# SCH_N3_FLIGHT_COMPUTER_2023-10-18.net
KiCad netlist of a schematic drawn in EasyEDA
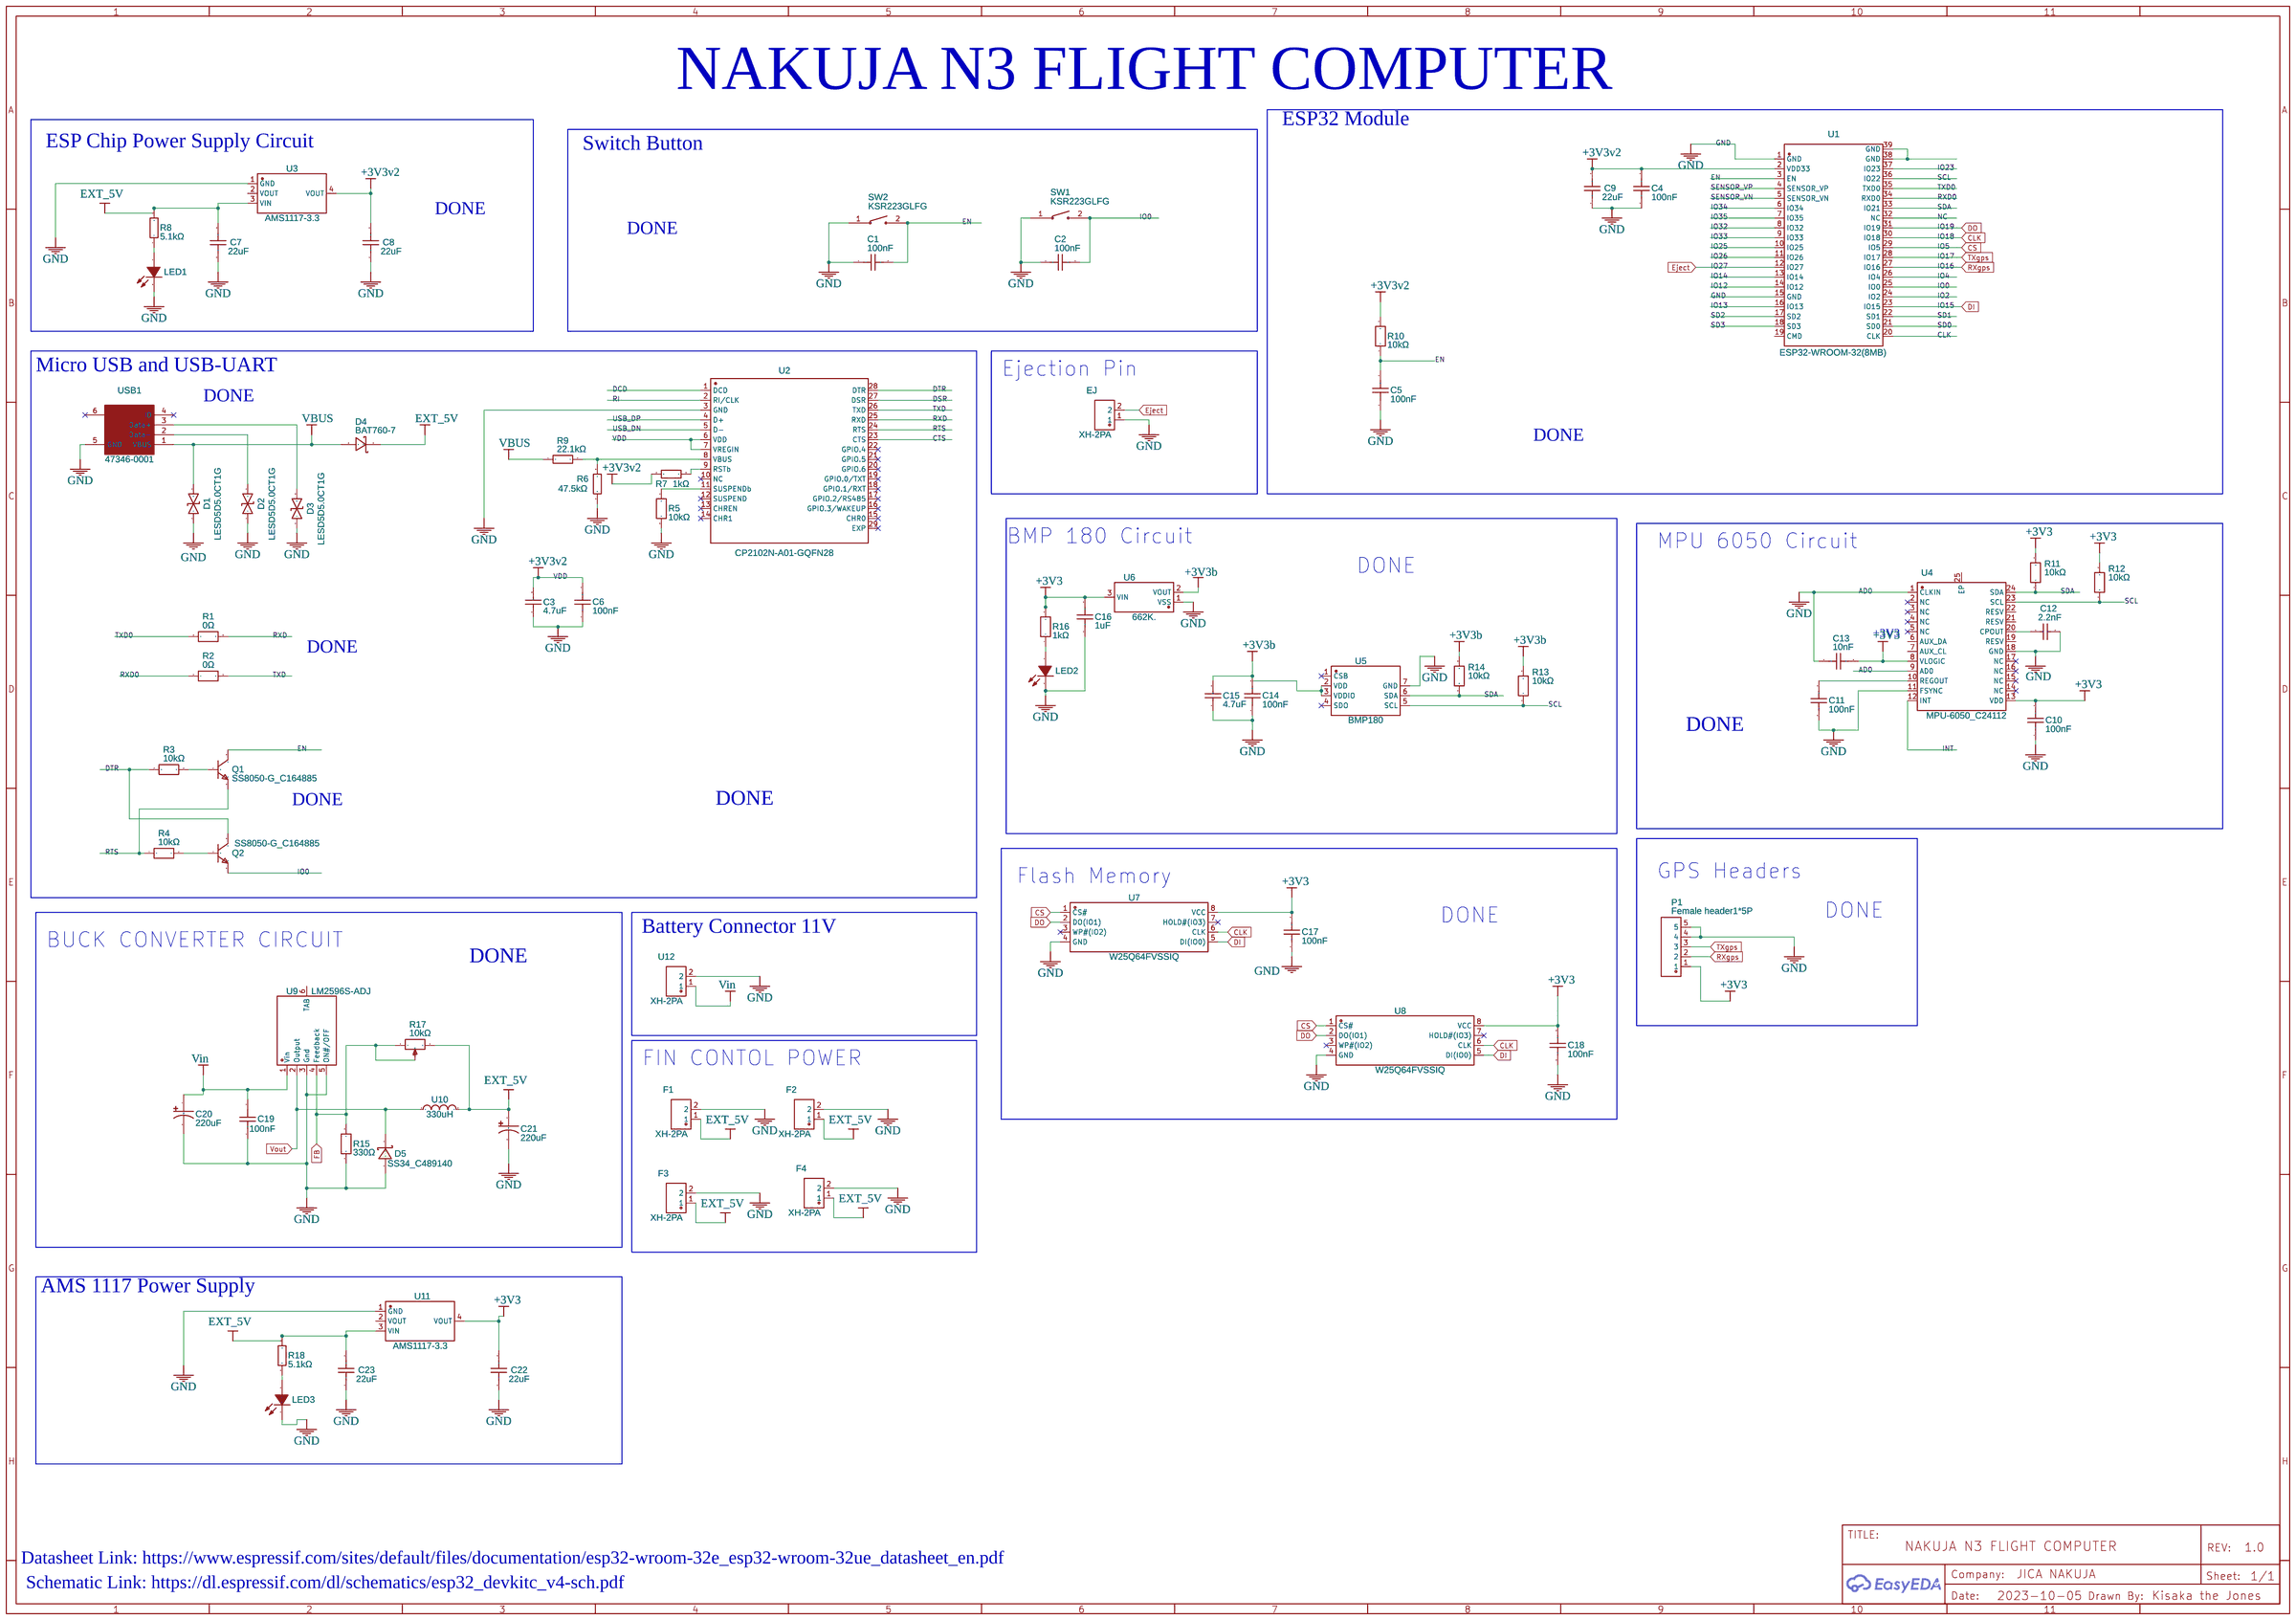
[diagram p0: schematic sheet]

(export (version "E")
  (design (tool "Eeschema 10.0.6"))
  (components
    (comp (ref "C1")
      (value "100nF")
      (fields
        (field (name "Manufacturer Part") "CL05A104KA5NNND")
        (field (name "Manufacturer") "SAMSUNG(三星)")
      )
      (libsource (lib "") (part "CL05A104KA5NNND_1"))
    )
    (comp (ref "C2")
      (value "100nF")
      (fields
        (field (name "Manufacturer Part") "CL05A104KA5NNND")
        (field (name "Manufacturer") "SAMSUNG(三星)")
      )
      (libsource (lib "") (part "CL05A104KA5NNND_1"))
    )
    (comp (ref "C3")
      (value "4.7uF")
      (fields
        (field (name "Manufacturer Part") "CL21B475KPFNNNE")
        (field (name "Manufacturer") "SAMSUNG(三星)")
      )
      (libsource (lib "") (part "CL21B475KPFNNNE"))
    )
    (comp (ref "C4")
      (value "100nF")
      (fields
        (field (name "Manufacturer Part") "CL05A104KA5NNND")
        (field (name "Manufacturer") "SAMSUNG(三星)")
      )
      (libsource (lib "") (part "CL05A104KA5NNND"))
    )
    (comp (ref "C5")
      (value "100nF")
      (fields
        (field (name "Manufacturer Part") "CL05A104KA5NNND")
        (field (name "Manufacturer") "SAMSUNG(三星)")
      )
      (libsource (lib "") (part "CL05A104KA5NNND"))
    )
    (comp (ref "C6")
      (value "100nF")
      (fields
        (field (name "Manufacturer Part") "CL05A104KA5NNND")
        (field (name "Manufacturer") "SAMSUNG(三星)")
      )
      (libsource (lib "") (part "CL05A104KA5NNND"))
    )
    (comp (ref "C7")
      (value "22uF")
      (fields
        (field (name "Manufacturer Part") "CL21A226MAQNNNF")
        (field (name "Manufacturer") "SAMSUNG(三星)")
      )
      (libsource (lib "") (part "CL21A226MAQNNNF"))
    )
    (comp (ref "C8")
      (value "22uF")
      (fields
        (field (name "Manufacturer Part") "CL21A226MAQNNNF")
        (field (name "Manufacturer") "SAMSUNG(三星)")
      )
      (libsource (lib "") (part "CL21A226MAQNNNF"))
    )
    (comp (ref "C9")
      (value "22uF")
      (fields
        (field (name "Manufacturer Part") "CL21A226MAQNNNF")
        (field (name "Manufacturer") "SAMSUNG(三星)")
      )
      (libsource (lib "") (part "CL21A226MAQNNNF"))
    )
    (comp (ref "C10")
      (value "100nF")
      (fields
        (field (name "Manufacturer Part") "CL05A104KA5NNND")
        (field (name "Manufacturer") "SAMSUNG(三星)")
      )
      (libsource (lib "") (part "CL05A104KA5NNND"))
    )
    (comp (ref "C11")
      (value "100nF")
      (fields
        (field (name "Manufacturer Part") "CL05A104KA5NNND")
        (field (name "Manufacturer") "SAMSUNG(三星)")
      )
      (libsource (lib "") (part "CL05A104KA5NNND"))
    )
    (comp (ref "C12")
      (value "2.2nF")
      (fields (field (name "Manufacturer Part") "0805B222K500NT") (field (name "Manufacturer") "FH(风华)"))
      (libsource (lib "") (part "0805B222K500NT"))
    )
    (comp (ref "C13")
      (value "10nF")
      (fields
        (field (name "Manufacturer Part") "CC0805KRX7R9BB103")
        (field (name "Manufacturer") "YAGEO(国巨)")
      )
      (libsource (lib "") (part "CC0805KRX7R9BB103"))
    )
    (comp (ref "C14")
      (value "100nF")
      (fields
        (field (name "Manufacturer Part") "CL05A104KA5NNND")
        (field (name "Manufacturer") "SAMSUNG(三星)")
      )
      (libsource (lib "") (part "CL05A104KA5NNND"))
    )
    (comp (ref "C15")
      (value "4.7uF")
      (fields
        (field (name "Manufacturer Part") "CL21B475KPFNNNE")
        (field (name "Manufacturer") "SAMSUNG(三星)")
      )
      (libsource (lib "") (part "CL21B475KPFNNNE"))
    )
    (comp (ref "C16")
      (value "1uF")
      (fields
        (field (name "Manufacturer Part") "CL21B105KBFNFNE")
        (field (name "Manufacturer") "SAMSUNG(三星)")
      )
      (libsource (lib "") (part "CL21B105KBFNFNE"))
    )
    (comp (ref "C17")
      (value "100nF")
      (fields
        (field (name "Manufacturer Part") "CL05A104KA5NNND")
        (field (name "Manufacturer") "SAMSUNG(三星)")
      )
      (libsource (lib "") (part "CL05A104KA5NNND"))
    )
    (comp (ref "C18")
      (value "100nF")
      (fields
        (field (name "Manufacturer Part") "CL05A104KA5NNND")
        (field (name "Manufacturer") "SAMSUNG(三星)")
      )
      (libsource (lib "") (part "CL05A104KA5NNND"))
    )
    (comp (ref "C19")
      (value "100nF")
      (fields
        (field (name "Manufacturer Part") "CL05A104KA5NNND")
        (field (name "Manufacturer") "SAMSUNG(三星)")
      )
      (libsource (lib "") (part "CL05A104KA5NNND"))
    )
    (comp (ref "C20")
      (value "220uF")
      (fields (field (name "Manufacturer Part") "EEEFP1H221AP") (field (name "Manufacturer") "PANASONIC(松下)"))
      (libsource (lib "") (part "EEEFP1H221AP_1"))
    )
    (comp (ref "C21")
      (value "220uF")
      (fields (field (name "Manufacturer Part") "EEEFP1H221AP") (field (name "Manufacturer") "PANASONIC(松下)"))
      (libsource (lib "") (part "EEEFP1H221AP"))
    )
    (comp (ref "C22")
      (value "22uF")
      (fields
        (field (name "Manufacturer Part") "CL21A226MAQNNNF")
        (field (name "Manufacturer") "SAMSUNG(三星)")
      )
      (libsource (lib "") (part "CL21A226MAQNNNF"))
    )
    (comp (ref "C23")
      (value "22uF")
      (fields
        (field (name "Manufacturer Part") "CL21A226MAQNNNF")
        (field (name "Manufacturer") "SAMSUNG(三星)")
      )
      (libsource (lib "") (part "CL21A226MAQNNNF"))
    )
    (comp (ref "D1")
      (value "LESD5D5.0CT1G")
      (fields (field (name "Manufacturer") "LRC(乐山无线电)"))
      (libsource (lib "") (part "LESD5D5.0CT1G"))
    )
    (comp (ref "D2")
      (value "LESD5D5.0CT1G")
      (fields (field (name "Manufacturer") "LRC(乐山无线电)"))
      (libsource (lib "") (part "LESD5D5.0CT1G"))
    )
    (comp (ref "D3")
      (value "LESD5D5.0CT1G")
      (fields (field (name "Manufacturer") "LRC(乐山无线电)"))
      (libsource (lib "") (part "LESD5D5.0CT1G"))
    )
    (comp (ref "D4")
      (value "BAT760-7")
      (fields (field (name "Manufacturer") "DIODES(美台)"))
      (libsource (lib "") (part "BAT760-7"))
    )
    (comp (ref "D5")
      (value "SS34_C489140")
      (fields (field (name "Manufacturer Part") "SS34") (field (name "Manufacturer") "KEXIN(科信)"))
      (libsource (lib "") (part "SS34_C489140"))
    )
    (comp (ref "EJ")
      (value "XH-2PA")
      (fields (field (name "Manufacturer") "ZHOURI(洲日)"))
      (libsource (lib "") (part "XH-2PA_2"))
    )
    (comp (ref "F1")
      (value "XH-2PA")
      (fields (field (name "Manufacturer") "ZHOURI(洲日)"))
      (libsource (lib "") (part "XH-2PA"))
    )
    (comp (ref "F2")
      (value "XH-2PA")
      (fields (field (name "Manufacturer") "ZHOURI(洲日)"))
      (libsource (lib "") (part "XH-2PA"))
    )
    (comp (ref "F3")
      (value "XH-2PA")
      (fields (field (name "Manufacturer") "ZHOURI(洲日)"))
      (libsource (lib "") (part "XH-2PA"))
    )
    (comp (ref "F4")
      (value "XH-2PA")
      (fields (field (name "Manufacturer") "ZHOURI(洲日)"))
      (libsource (lib "") (part "XH-2PA"))
    )
    (comp (ref "LED1")
      (value "15-21SOC/TR8")
      (fields (field (name "Manufacturer") "EVERLIGHT(亿光)"))
      (libsource (lib "") (part "15-21SOC/TR8"))
    )
    (comp (ref "LED2")
      (value "15-21SOC/TR8")
      (fields (field (name "Manufacturer") "EVERLIGHT(亿光)"))
      (libsource (lib "") (part "15-21SOC/TR8"))
    )
    (comp (ref "LED3")
      (value "15-21SOC/TR8")
      (fields (field (name "Manufacturer") "EVERLIGHT(亿光)"))
      (libsource (lib "") (part "15-21SOC/TR8"))
    )
    (comp (ref "P1")
      (value "Female header1*5P")
      (fields (field (name "Manufacturer Part") "2.0-1*5P母") (field (name "Manufacturer") "BOOMELE(博穆精密)"))
      (libsource (lib "") (part "Female header1*5P"))
    )
    (comp (ref "Q1")
      (value "SS8050-G_C164885")
      (fields (field (name "Manufacturer Part") "SS8050-G") (field (name "Manufacturer") "CJ(江苏长电/长晶)"))
      (libsource (lib "") (part "SS8050-G_C164885"))
    )
    (comp (ref "Q2")
      (value "SS8050-G_C164885")
      (fields (field (name "Manufacturer Part") "SS8050-G") (field (name "Manufacturer") "CJ(江苏长电/长晶)"))
      (libsource (lib "") (part "SS8050-G_C164885"))
    )
    (comp (ref "R1")
      (value "0Ω")
      (fields (field (name "Manufacturer Part") "SY0402JN0RP") (field (name "Manufacturer") "SANYEAR(叁叶源)"))
      (libsource (lib "") (part "SY0402JN0RP"))
    )
    (comp (ref "R2")
      (value "0Ω")
      (fields (field (name "Manufacturer Part") "SY0402JN0RP") (field (name "Manufacturer") "SANYEAR(叁叶源)"))
      (libsource (lib "") (part "SY0402JN0RP"))
    )
    (comp (ref "R3")
      (value "10kΩ")
      (fields
        (field (name "Manufacturer Part") "RMC1/10-103JTP")
        (field (name "Manufacturer") "KAMAYA(釜屋電機)")
      )
      (libsource (lib "") (part "RMC1/10-103JTP_1"))
    )
    (comp (ref "R4")
      (value "10kΩ")
      (fields
        (field (name "Manufacturer Part") "RMC1/10-103JTP")
        (field (name "Manufacturer") "KAMAYA(釜屋電機)")
      )
      (libsource (lib "") (part "RMC1/10-103JTP_1"))
    )
    (comp (ref "R5")
      (value "10kΩ")
      (fields
        (field (name "Manufacturer Part") "RMC1/10-103JTP")
        (field (name "Manufacturer") "KAMAYA(釜屋電機)")
      )
      (libsource (lib "") (part "RMC1/10-103JTP_2"))
    )
    (comp (ref "R6")
      (value "47.5kΩ")
      (fields
        (field (name "Manufacturer Part") "0402WGF4752TCE")
        (field (name "Manufacturer") "UNI-ROYAL(厚声)")
      )
      (libsource (lib "") (part "0402WGF4752TCE"))
    )
    (comp (ref "R7")
      (value "1kΩ")
      (fields
        (field (name "Manufacturer Part") "0402WGF1001TCE")
        (field (name "Manufacturer") "UNI-ROYAL(厚声)")
      )
      (libsource (lib "") (part "0402WGF1001TCE"))
    )
    (comp (ref "R8")
      (value "5.1kΩ")
      (fields
        (field (name "Manufacturer Part") "0402WGJ0512TCE")
        (field (name "Manufacturer") "UNI-ROYAL(厚声)")
      )
      (libsource (lib "") (part "0402WGJ0512TCE"))
    )
    (comp (ref "R9")
      (value "22.1kΩ")
      (fields
        (field (name "Manufacturer Part") "0402WGF2212TCE")
        (field (name "Manufacturer") "UNI-ROYAL(厚声)")
      )
      (libsource (lib "") (part "0402WGF2212TCE"))
    )
    (comp (ref "R10")
      (value "10kΩ")
      (fields
        (field (name "Manufacturer Part") "RMC1/10-103JTP")
        (field (name "Manufacturer") "KAMAYA(釜屋電機)")
      )
      (libsource (lib "") (part "RMC1/10-103JTP"))
    )
    (comp (ref "R11")
      (value "10kΩ")
      (fields
        (field (name "Manufacturer Part") "RMC1/10-103JTP")
        (field (name "Manufacturer") "KAMAYA(釜屋電機)")
      )
      (libsource (lib "") (part "RMC1/10-103JTP"))
    )
    (comp (ref "R12")
      (value "10kΩ")
      (fields
        (field (name "Manufacturer Part") "RMC1/10-103JTP")
        (field (name "Manufacturer") "KAMAYA(釜屋電機)")
      )
      (libsource (lib "") (part "RMC1/10-103JTP"))
    )
    (comp (ref "R13")
      (value "10kΩ")
      (fields
        (field (name "Manufacturer Part") "RMC1/10-103JTP")
        (field (name "Manufacturer") "KAMAYA(釜屋電機)")
      )
      (libsource (lib "") (part "RMC1/10-103JTP"))
    )
    (comp (ref "R14")
      (value "10kΩ")
      (fields
        (field (name "Manufacturer Part") "RMC1/10-103JTP")
        (field (name "Manufacturer") "KAMAYA(釜屋電機)")
      )
      (libsource (lib "") (part "RMC1/10-103JTP"))
    )
    (comp (ref "R15")
      (value "330Ω")
      (fields
        (field (name "Manufacturer Part") "SYLE1206JN330RP")
        (field (name "Manufacturer") "SANYEAR(叁叶源)")
      )
      (libsource (lib "") (part "SYLE1206JN330RP"))
    )
    (comp (ref "R16")
      (value "1kΩ")
      (fields (field (name "Manufacturer Part") "WR08X102JTL") (field (name "Manufacturer") "Walsin(华新科)"))
      (libsource (lib "") (part "WR08X102 JTL"))
    )
    (comp (ref "R17")
      (value "10kΩ")
      (fields (field (name "Manufacturer Part") "3296W-1-103LF") (field (name "Manufacturer") "BOURNS"))
      (libsource (lib "") (part "3296W-1-103LF"))
    )
    (comp (ref "R18")
      (value "5.1kΩ")
      (fields
        (field (name "Manufacturer Part") "0402WGJ0512TCE")
        (field (name "Manufacturer") "UNI-ROYAL(厚声)")
      )
      (libsource (lib "") (part "0402WGJ0512TCE"))
    )
    (comp (ref "SW1")
      (value "KSR223GLFG")
      (fields (field (name "Manufacturer") "C&K"))
      (libsource (lib "") (part "KSR223GLFG"))
    )
    (comp (ref "SW2")
      (value "KSR223GLFG")
      (fields (field (name "Manufacturer") "C&K"))
      (libsource (lib "") (part "KSR223GLFG"))
    )
    (comp (ref "U1")
      (value "ESP32-WROOM-32(8MB)")
      (fields
        (field (name "Manufacturer Part") "ESP32-WROOM-32-N8")
        (field (name "Manufacturer") "ESPRESSIF(乐鑫)")
      )
      (libsource (lib "") (part "ESP32-WROOM-32(8MB)"))
    )
    (comp (ref "U2")
      (value "CP2102N-A01-GQFN28")
      (fields
        (field (name "Manufacturer Part") "CP2102N-A01-GQFN28R")
        (field (name "Manufacturer") "SILICON LABS(芯科)")
      )
      (libsource (lib "") (part "CP2102N-A01-GQFN28"))
    )
    (comp (ref "U3")
      (value "AMS1117-3.3")
      (fields (field (name "Manufacturer") "AMS"))
      (libsource (lib "") (part "AMS1117-3.3"))
    )
    (comp (ref "U4")
      (value "MPU-6050_C24112")
      (fields
        (field (name "Manufacturer Part") "MPU-6050")
        (field (name "Manufacturer") "TDK InvenSense(应美盛)")
      )
      (libsource (lib "") (part "MPU-6050_C24112"))
    )
    (comp (ref "U5")
      (value "BMP180")
      (fields (field (name "Manufacturer") "Bosch(博世)"))
      (libsource (lib "") (part "BMP180"))
    )
    (comp (ref "U6")
      (value "662K.")
      (fields (field (name "Manufacturer") "FM(富满)"))
      (libsource (lib "") (part "662K."))
    )
    (comp (ref "U7")
      (value "W25Q64FVSSIQ")
      (fields (field (name "Manufacturer") "WINBOND(华邦)"))
      (libsource (lib "") (part "W25Q64FVSSIQ"))
    )
    (comp (ref "U8")
      (value "W25Q64FVSSIQ")
      (fields (field (name "Manufacturer") "WINBOND(华邦)"))
      (libsource (lib "") (part "W25Q64FVSSIQ"))
    )
    (comp (ref "U9")
      (value "LM2596S-ADJ")
      (fields (field (name "Manufacturer") "UMW(友台半导体)"))
      (libsource (lib "") (part "LM2596S-ADJ"))
    )
    (comp (ref "U10")
      (value "330uH")
      (fields (field (name "Manufacturer Part") "SLF12575T-331M1R0-H") (field (name "Manufacturer") "TDK"))
      (libsource (lib "") (part "SLF12575T-331M1R0-H"))
    )
    (comp (ref "U11")
      (value "AMS1117-3.3")
      (fields (field (name "Manufacturer") "AMS"))
      (libsource (lib "") (part "AMS1117-3.3"))
    )
    (comp (ref "U12")
      (value "XH-2PA")
      (fields (field (name "Manufacturer") "ZHOURI(洲日)"))
      (libsource (lib "") (part "XH-2PA_1"))
    )
    (comp (ref "USB1")
      (value "47346-0001")
      (fields (field (name "Manufacturer Part") "473460001") (field (name "Manufacturer") "MOLEX"))
      (libsource (lib "") (part "47346-0001"))
    )
  )
  (nets
    (net (code "1") (name "+3V3") (class "Default")
      (node (ref "C10") (pin "2") (pinfunction "2_2") (pintype "unspecified"))
      (node (ref "C13") (pin "2") (pinfunction "2_2") (pintype "unspecified"))
      (node (ref "C16") (pin "2") (pinfunction "2_2") (pintype "unspecified"))
      (node (ref "C17") (pin "2") (pinfunction "2_2") (pintype "unspecified"))
      (node (ref "C18") (pin "2") (pinfunction "2_2") (pintype "unspecified"))
      (node (ref "C22") (pin "2") (pinfunction "2_2") (pintype "unspecified"))
      (node (ref "P1") (pin "1") (pinfunction "1_1") (pintype "unspecified"))
      (node (ref "R11") (pin "2") (pinfunction "2_2") (pintype "unspecified"))
      (node (ref "R12") (pin "2") (pinfunction "2_2") (pintype "unspecified"))
      (node (ref "R16") (pin "2") (pinfunction "2_2") (pintype "unspecified"))
      (node (ref "U11") (pin "4") (pinfunction "VOUT_4") (pintype "unspecified"))
      (node (ref "U4") (pin "13") (pinfunction "VDD_13") (pintype "unspecified"))
      (node (ref "U4") (pin "8") (pinfunction "VLOGIC_8") (pintype "unspecified"))
      (node (ref "U6") (pin "3") (pinfunction "VIN_3") (pintype "unspecified"))
      (node (ref "U7") (pin "8") (pinfunction "VCC_8") (pintype "unspecified"))
      (node (ref "U8") (pin "8") (pinfunction "VCC_8") (pintype "unspecified"))
    )
    (net (code "2") (name "+3V3b") (class "Default")
      (node (ref "C14") (pin "2") (pinfunction "2_2") (pintype "unspecified"))
      (node (ref "C15") (pin "2") (pinfunction "2_2") (pintype "input"))
      (node (ref "R13") (pin "2") (pinfunction "2_2") (pintype "unspecified"))
      (node (ref "R14") (pin "2") (pinfunction "2_2") (pintype "unspecified"))
      (node (ref "U5") (pin "2") (pinfunction "VDD_2") (pintype "unspecified"))
      (node (ref "U5") (pin "3") (pinfunction "VDDIO_3") (pintype "unspecified"))
      (node (ref "U6") (pin "2") (pinfunction "VOUT_2") (pintype "unspecified"))
    )
    (net (code "3") (name "+3V3v2") (class "Default")
      (node (ref "C3") (pin "2") (pinfunction "2_2") (pintype "input"))
      (node (ref "C4") (pin "2") (pinfunction "2_2") (pintype "unspecified"))
      (node (ref "C6") (pin "2") (pinfunction "2_2") (pintype "unspecified"))
      (node (ref "C8") (pin "2") (pinfunction "2_2") (pintype "unspecified"))
      (node (ref "C9") (pin "2") (pinfunction "2_2") (pintype "unspecified"))
      (node (ref "R10") (pin "2") (pinfunction "2_2") (pintype "unspecified"))
      (node (ref "R7") (pin "1") (pinfunction "1_1") (pintype "input"))
      (node (ref "U1") (pin "2") (pinfunction "VDD33_2") (pintype "unspecified"))
      (node (ref "U2") (pin "6") (pinfunction "VDD_6") (pintype "unspecified"))
      (node (ref "U2") (pin "7") (pinfunction "VREGIN_7") (pintype "unspecified"))
      (node (ref "U3") (pin "4") (pinfunction "VOUT_4") (pintype "unspecified"))
    )
    (net (code "4") (name "/CTS") (class "Default")
      (node (ref "U2") (pin "23") (pinfunction "CTS_23") (pintype "unspecified"))
    )
    (net (code "5") (name "/DCD") (class "Default")
      (node (ref "U2") (pin "1") (pinfunction "DCD_1") (pintype "unspecified"))
    )
    (net (code "6") (name "/DSR") (class "Default")
      (node (ref "U2") (pin "27") (pinfunction "DSR_27") (pintype "unspecified"))
    )
    (net (code "7") (name "/DTR") (class "Default")
      (node (ref "Q2") (pin "3") (pinfunction "C_3") (pintype "unspecified"))
      (node (ref "R3") (pin "1") (pinfunction "1_1") (pintype "unspecified"))
      (node (ref "U2") (pin "28") (pinfunction "DTR_28") (pintype "unspecified"))
    )
    (net (code "8") (name "/EN") (class "Default")
      (node (ref "C1") (pin "2") (pinfunction "2_2") (pintype "unspecified"))
      (node (ref "C5") (pin "2") (pinfunction "2_2") (pintype "unspecified"))
      (node (ref "Q1") (pin "3") (pinfunction "C_3") (pintype "unspecified"))
      (node (ref "R10") (pin "1") (pinfunction "1_1") (pintype "unspecified"))
      (node (ref "SW2") (pin "2") (pinfunction "2_2") (pintype "unspecified"))
      (node (ref "U1") (pin "3") (pinfunction "EN_3") (pintype "unspecified"))
    )
    (net (code "9") (name "/INT") (class "Default")
      (node (ref "U4") (pin "12") (pinfunction "INT_12") (pintype "unspecified"))
    )
    (net (code "10") (name "/IO0") (class "Default")
      (node (ref "C2") (pin "2") (pinfunction "2_2") (pintype "unspecified"))
      (node (ref "Q2") (pin "2") (pinfunction "E_2") (pintype "unspecified"))
      (node (ref "SW1") (pin "2") (pinfunction "2_2") (pintype "unspecified"))
      (node (ref "U1") (pin "25") (pinfunction "IO0_25") (pintype "unspecified"))
    )
    (net (code "11") (name "/IO2") (class "Default")
      (node (ref "U1") (pin "24") (pinfunction "IO2_24") (pintype "unspecified"))
    )
    (net (code "12") (name "/IO4") (class "Default")
      (node (ref "U1") (pin "26") (pinfunction "IO4_26") (pintype "unspecified"))
    )
    (net (code "13") (name "/IO12") (class "Default")
      (node (ref "U1") (pin "14") (pinfunction "IO12_14") (pintype "unspecified"))
    )
    (net (code "14") (name "/IO13") (class "Default")
      (node (ref "U1") (pin "16") (pinfunction "IO13_16") (pintype "unspecified"))
    )
    (net (code "15") (name "/IO14") (class "Default")
      (node (ref "U1") (pin "13") (pinfunction "IO14_13") (pintype "unspecified"))
    )
    (net (code "16") (name "/IO23") (class "Default")
      (node (ref "U1") (pin "37") (pinfunction "IO23_37") (pintype "unspecified"))
    )
    (net (code "17") (name "/IO25") (class "Default")
      (node (ref "U1") (pin "10") (pinfunction "IO25_10") (pintype "unspecified"))
    )
    (net (code "18") (name "/IO26") (class "Default")
      (node (ref "U1") (pin "11") (pinfunction "IO26_11") (pintype "unspecified"))
    )
    (net (code "19") (name "/IO32") (class "Default")
      (node (ref "U1") (pin "8") (pinfunction "IO32_8") (pintype "unspecified"))
    )
    (net (code "20") (name "/IO33") (class "Default")
      (node (ref "U1") (pin "9") (pinfunction "IO33_9") (pintype "unspecified"))
    )
    (net (code "21") (name "/IO34") (class "Default")
      (node (ref "U1") (pin "6") (pinfunction "IO34_6") (pintype "unspecified"))
    )
    (net (code "22") (name "/IO35") (class "Default")
      (node (ref "U1") (pin "7") (pinfunction "IO35_7") (pintype "unspecified"))
    )
    (net (code "23") (name "/NC") (class "Default")
      (node (ref "U1") (pin "32") (pinfunction "NC_32") (pintype "unspecified"))
    )
    (net (code "24") (name "/RI") (class "Default")
      (node (ref "U2") (pin "2") (pinfunction "RI/CLK_2") (pintype "unspecified"))
    )
    (net (code "25") (name "/RTS") (class "Default")
      (node (ref "Q1") (pin "2") (pinfunction "E_2") (pintype "unspecified"))
      (node (ref "R4") (pin "1") (pinfunction "1_1") (pintype "unspecified"))
      (node (ref "U2") (pin "24") (pinfunction "RTS_24") (pintype "unspecified"))
    )
    (net (code "26") (name "/RXD") (class "Default")
      (node (ref "R1") (pin "2") (pinfunction "2_2") (pintype "unspecified"))
      (node (ref "U2") (pin "25") (pinfunction "RXD_25") (pintype "unspecified"))
    )
    (net (code "27") (name "/RXD0") (class "Default")
      (node (ref "R2") (pin "1") (pinfunction "1_1") (pintype "unspecified"))
      (node (ref "U1") (pin "34") (pinfunction "RXD0_34") (pintype "unspecified"))
    )
    (net (code "28") (name "/SCL") (class "Default")
      (node (ref "R12") (pin "1") (pinfunction "1_1") (pintype "unspecified"))
      (node (ref "R13") (pin "1") (pinfunction "1_1") (pintype "unspecified"))
      (node (ref "U1") (pin "36") (pinfunction "IO22_36") (pintype "unspecified"))
      (node (ref "U4") (pin "23") (pinfunction "SCL_23") (pintype "unspecified"))
      (node (ref "U5") (pin "5") (pinfunction "SCL_5") (pintype "unspecified"))
    )
    (net (code "29") (name "/SD0") (class "Default")
      (node (ref "U1") (pin "21") (pinfunction "SD0_21") (pintype "unspecified"))
    )
    (net (code "30") (name "/SD1") (class "Default")
      (node (ref "U1") (pin "22") (pinfunction "SD1_22") (pintype "unspecified"))
    )
    (net (code "31") (name "/SD2") (class "Default")
      (node (ref "U1") (pin "17") (pinfunction "SD2_17") (pintype "unspecified"))
    )
    (net (code "32") (name "/SD3") (class "Default")
      (node (ref "U1") (pin "18") (pinfunction "SD3_18") (pintype "unspecified"))
    )
    (net (code "33") (name "/SDA") (class "Default")
      (node (ref "R11") (pin "1") (pinfunction "1_1") (pintype "unspecified"))
      (node (ref "R14") (pin "1") (pinfunction "1_1") (pintype "unspecified"))
      (node (ref "U1") (pin "33") (pinfunction "IO21_33") (pintype "unspecified"))
      (node (ref "U4") (pin "24") (pinfunction "SDA_24") (pintype "unspecified"))
      (node (ref "U5") (pin "6") (pinfunction "SDA_6") (pintype "unspecified"))
    )
    (net (code "34") (name "/SENSOR_VN") (class "Default")
      (node (ref "U1") (pin "5") (pinfunction "SENSOR_VN_5") (pintype "unspecified"))
    )
    (net (code "35") (name "/SENSOR_VP") (class "Default")
      (node (ref "U1") (pin "4") (pinfunction "SENSOR_VP_4") (pintype "unspecified"))
    )
    (net (code "36") (name "/TXD") (class "Default")
      (node (ref "R2") (pin "2") (pinfunction "2_2") (pintype "unspecified"))
      (node (ref "U2") (pin "26") (pinfunction "TXD_26") (pintype "unspecified"))
    )
    (net (code "37") (name "/TXD0") (class "Default")
      (node (ref "R1") (pin "1") (pinfunction "1_1") (pintype "unspecified"))
      (node (ref "U1") (pin "35") (pinfunction "TXD0_35") (pintype "unspecified"))
    )
    (net (code "38") (name "/USB_DN") (class "Default")
      (node (ref "U2") (pin "5") (pinfunction "D-_5") (pintype "unspecified"))
    )
    (net (code "39") (name "/USB_DP") (class "Default")
      (node (ref "U2") (pin "4") (pinfunction "D+_4") (pintype "unspecified"))
    )
    (net (code "40") (name "CLK") (class "Default")
      (node (ref "U1") (pin "20") (pinfunction "CLK_20") (pintype "unspecified"))
      (node (ref "U1") (pin "30") (pinfunction "IO18_30") (pintype "unspecified"))
      (node (ref "U7") (pin "6") (pinfunction "CLK_6") (pintype "unspecified"))
      (node (ref "U8") (pin "6") (pinfunction "CLK_6") (pintype "unspecified"))
    )
    (net (code "41") (name "CS") (class "Default")
      (node (ref "U1") (pin "29") (pinfunction "IO5_29") (pintype "unspecified"))
      (node (ref "U7") (pin "1") (pinfunction "CS#_1") (pintype "unspecified"))
      (node (ref "U8") (pin "1") (pinfunction "CS#_1") (pintype "unspecified"))
    )
    (net (code "42") (name "DI") (class "Default")
      (node (ref "U1") (pin "23") (pinfunction "IO15_23") (pintype "unspecified"))
      (node (ref "U7") (pin "5") (pinfunction "DI(IO0)_5") (pintype "unspecified"))
      (node (ref "U8") (pin "5") (pinfunction "DI(IO0)_5") (pintype "unspecified"))
    )
    (net (code "43") (name "DO") (class "Default")
      (node (ref "U1") (pin "31") (pinfunction "IO19_31") (pintype "unspecified"))
      (node (ref "U7") (pin "2") (pinfunction "DO(IO1)_2") (pintype "unspecified"))
      (node (ref "U8") (pin "2") (pinfunction "DO(IO1)_2") (pintype "unspecified"))
    )
    (net (code "44") (name "EXT_5V") (class "Default")
      (node (ref "C21") (pin "1") (pinfunction "1_1") (pintype "unspecified"))
      (node (ref "C23") (pin "2") (pinfunction "2_2") (pintype "unspecified"))
      (node (ref "C7") (pin "2") (pinfunction "2_2") (pintype "unspecified"))
      (node (ref "D4") (pin "1") (pinfunction "1_1") (pintype "unspecified"))
      (node (ref "F1") (pin "1") (pinfunction "1_1") (pintype "unspecified"))
      (node (ref "F2") (pin "1") (pinfunction "1_1") (pintype "unspecified"))
      (node (ref "F3") (pin "1") (pinfunction "1_1") (pintype "unspecified"))
      (node (ref "F4") (pin "1") (pinfunction "1_1") (pintype "unspecified"))
      (node (ref "R17") (pin "3") (pinfunction "3_3") (pintype "input"))
      (node (ref "R18") (pin "2") (pinfunction "2_2") (pintype "input"))
      (node (ref "R8") (pin "2") (pinfunction "2_2") (pintype "input"))
      (node (ref "U10") (pin "2") (pinfunction "2_2") (pintype "unspecified"))
      (node (ref "U11") (pin "3") (pinfunction "VIN_3") (pintype "unspecified"))
      (node (ref "U3") (pin "3") (pinfunction "VIN_3") (pintype "unspecified"))
    )
    (net (code "45") (name "Eject") (class "Default")
      (node (ref "EJ") (pin "2") (pinfunction "2_2") (pintype "unspecified"))
      (node (ref "U1") (pin "12") (pinfunction "IO27_12") (pintype "unspecified"))
    )
    (net (code "46") (name "FB") (class "Default")
      (node (ref "R15") (pin "2") (pinfunction "2_2") (pintype "unspecified"))
      (node (ref "R17") (pin "1") (pinfunction "1_1") (pintype "input"))
      (node (ref "R17") (pin "2") (pinfunction "2_2") (pintype "input"))
      (node (ref "U9") (pin "4") (pinfunction "Feedback_4") (pintype "unspecified"))
    )
    (net (code "47") (name "GND") (class "Default")
      (node (ref "C1") (pin "1") (pinfunction "1_1") (pintype "unspecified"))
      (node (ref "C10") (pin "1") (pinfunction "1_1") (pintype "unspecified"))
      (node (ref "C11") (pin "1") (pinfunction "1_1") (pintype "unspecified"))
      (node (ref "C12") (pin "2") (pinfunction "2_2") (pintype "input"))
      (node (ref "C13") (pin "1") (pinfunction "1_1") (pintype "unspecified"))
      (node (ref "C14") (pin "1") (pinfunction "1_1") (pintype "unspecified"))
      (node (ref "C15") (pin "1") (pinfunction "1_1") (pintype "input"))
      (node (ref "C16") (pin "1") (pinfunction "1_1") (pintype "unspecified"))
      (node (ref "C17") (pin "1") (pinfunction "1_1") (pintype "unspecified"))
      (node (ref "C18") (pin "1") (pinfunction "1_1") (pintype "unspecified"))
      (node (ref "C19") (pin "1") (pinfunction "1_1") (pintype "unspecified"))
      (node (ref "C2") (pin "1") (pinfunction "1_1") (pintype "unspecified"))
      (node (ref "C20") (pin "2") (pinfunction "2_2") (pintype "unspecified"))
      (node (ref "C21") (pin "2") (pinfunction "2_2") (pintype "unspecified"))
      (node (ref "C22") (pin "1") (pinfunction "1_1") (pintype "unspecified"))
      (node (ref "C23") (pin "1") (pinfunction "1_1") (pintype "unspecified"))
      (node (ref "C3") (pin "1") (pinfunction "1_1") (pintype "input"))
      (node (ref "C4") (pin "1") (pinfunction "1_1") (pintype "unspecified"))
      (node (ref "C5") (pin "1") (pinfunction "1_1") (pintype "unspecified"))
      (node (ref "C6") (pin "1") (pinfunction "1_1") (pintype "unspecified"))
      (node (ref "C7") (pin "1") (pinfunction "1_1") (pintype "unspecified"))
      (node (ref "C8") (pin "1") (pinfunction "1_1") (pintype "unspecified"))
      (node (ref "C9") (pin "1") (pinfunction "1_1") (pintype "unspecified"))
      (node (ref "D1") (pin "1") (pinfunction "1_1") (pintype "unspecified"))
      (node (ref "D2") (pin "1") (pinfunction "1_1") (pintype "unspecified"))
      (node (ref "D3") (pin "1") (pinfunction "1_1") (pintype "unspecified"))
      (node (ref "D5") (pin "2") (pinfunction "A_2") (pintype "unspecified"))
      (node (ref "EJ") (pin "1") (pinfunction "1_1") (pintype "unspecified"))
      (node (ref "F1") (pin "2") (pinfunction "2_2") (pintype "unspecified"))
      (node (ref "F2") (pin "2") (pinfunction "2_2") (pintype "unspecified"))
      (node (ref "F3") (pin "2") (pinfunction "2_2") (pintype "unspecified"))
      (node (ref "F4") (pin "2") (pinfunction "2_2") (pintype "unspecified"))
      (node (ref "LED1") (pin "2") (pinfunction "K_2") (pintype "unspecified"))
      (node (ref "LED2") (pin "2") (pinfunction "K_2") (pintype "unspecified"))
      (node (ref "LED3") (pin "2") (pinfunction "K_2") (pintype "unspecified"))
      (node (ref "P1") (pin "4") (pinfunction "4_4") (pintype "unspecified"))
      (node (ref "P1") (pin "5") (pinfunction "5_5") (pintype "unspecified"))
      (node (ref "R15") (pin "1") (pinfunction "1_1") (pintype "unspecified"))
      (node (ref "R5") (pin "2") (pinfunction "2_2") (pintype "unspecified"))
      (node (ref "R6") (pin "1") (pinfunction "1_1") (pintype "input"))
      (node (ref "SW1") (pin "1") (pinfunction "1_1") (pintype "unspecified"))
      (node (ref "SW2") (pin "1") (pinfunction "1_1") (pintype "unspecified"))
      (node (ref "U1") (pin "1") (pinfunction "GND_1") (pintype "unspecified"))
      (node (ref "U1") (pin "15") (pinfunction "GND_15") (pintype "unspecified"))
      (node (ref "U11") (pin "1") (pinfunction "GND_1") (pintype "unspecified"))
      (node (ref "U12") (pin "2") (pinfunction "2_2") (pintype "unspecified"))
      (node (ref "U2") (pin "3") (pinfunction "GND_3") (pintype "unspecified"))
      (node (ref "U3") (pin "1") (pinfunction "GND_1") (pintype "unspecified"))
      (node (ref "U4") (pin "1") (pinfunction "CLKIN_1") (pintype "unspecified"))
      (node (ref "U4") (pin "11") (pinfunction "FSYNC_11") (pintype "unspecified"))
      (node (ref "U4") (pin "18") (pinfunction "GND_18") (pintype "unspecified"))
      (node (ref "U4") (pin "9") (pinfunction "AD0_9") (pintype "unspecified"))
      (node (ref "U5") (pin "7") (pinfunction "GND_7") (pintype "unspecified"))
      (node (ref "U6") (pin "1") (pinfunction "VSS_1") (pintype "unspecified"))
      (node (ref "U7") (pin "4") (pinfunction "GND_4") (pintype "unspecified"))
      (node (ref "U8") (pin "4") (pinfunction "GND_4") (pintype "unspecified"))
      (node (ref "U9") (pin "3") (pinfunction "Gnd_3") (pintype "unspecified"))
      (node (ref "U9") (pin "5") (pinfunction "ON#/OFF_5") (pintype "unspecified"))
      (node (ref "USB1") (pin "5") (pinfunction "GND_5") (pintype "bidirectional"))
    )
    (net (code "48") (name "Net-(LED1-A)") (class "Default")
      (node (ref "LED1") (pin "1") (pinfunction "A_1") (pintype "unspecified"))
      (node (ref "R8") (pin "1") (pinfunction "1_1") (pintype "input"))
    )
    (net (code "49") (name "Net-(LED2-A)") (class "Default")
      (node (ref "LED2") (pin "1") (pinfunction "A_1") (pintype "unspecified"))
      (node (ref "R16") (pin "1") (pinfunction "1_1") (pintype "unspecified"))
    )
    (net (code "50") (name "Net-(LED3-A)") (class "Default")
      (node (ref "LED3") (pin "1") (pinfunction "A_1") (pintype "unspecified"))
      (node (ref "R18") (pin "1") (pinfunction "1_1") (pintype "input"))
    )
    (net (code "51") (name "Net-(Q1-B)") (class "Default")
      (node (ref "Q1") (pin "1") (pinfunction "B_1") (pintype "unspecified"))
      (node (ref "R3") (pin "2") (pinfunction "2_2") (pintype "unspecified"))
    )
    (net (code "52") (name "Net-(Q2-B)") (class "Default")
      (node (ref "Q2") (pin "1") (pinfunction "B_1") (pintype "unspecified"))
      (node (ref "R4") (pin "2") (pinfunction "2_2") (pintype "unspecified"))
    )
    (net (code "53") (name "Net-(U1-GND-Pad38)") (class "Default")
      (node (ref "U1") (pin "38") (pinfunction "GND_38") (pintype "unspecified"))
      (node (ref "U1") (pin "39") (pinfunction "GND_39") (pintype "unspecified"))
    )
    (net (code "54") (name "Net-(U2-RSTb)") (class "Default")
      (node (ref "R7") (pin "2") (pinfunction "2_2") (pintype "input"))
      (node (ref "U2") (pin "9") (pinfunction "RSTb_9") (pintype "unspecified"))
    )
    (net (code "55") (name "Net-(U2-SUSPENDb)") (class "Default")
      (node (ref "R5") (pin "1") (pinfunction "1_1") (pintype "unspecified"))
      (node (ref "U2") (pin "11") (pinfunction "SUSPENDb_11") (pintype "unspecified"))
    )
    (net (code "56") (name "Net-(U2-VBUS)") (class "Default")
      (node (ref "R6") (pin "2") (pinfunction "2_2") (pintype "input"))
      (node (ref "R9") (pin "2") (pinfunction "2_2") (pintype "input"))
      (node (ref "U2") (pin "8") (pinfunction "VBUS_8") (pintype "unspecified"))
    )
    (net (code "57") (name "Net-(U4-CPOUT)") (class "Default")
      (node (ref "C12") (pin "1") (pinfunction "1_1") (pintype "input"))
      (node (ref "U4") (pin "20") (pinfunction "CPOUT_20") (pintype "unspecified"))
    )
    (net (code "58") (name "Net-(U4-REGOUT)") (class "Default")
      (node (ref "C11") (pin "2") (pinfunction "2_2") (pintype "unspecified"))
      (node (ref "U4") (pin "10") (pinfunction "REGOUT_10") (pintype "unspecified"))
    )
    (net (code "59") (name "Net-(USB1-Data+)") (class "Default")
      (node (ref "D3") (pin "2") (pinfunction "2_2") (pintype "unspecified"))
      (node (ref "USB1") (pin "3") (pinfunction "Data+_3") (pintype "input"))
    )
    (net (code "60") (name "Net-(USB1-Data-)") (class "Default")
      (node (ref "D2") (pin "2") (pinfunction "2_2") (pintype "unspecified"))
      (node (ref "USB1") (pin "2") (pinfunction "Data-_2") (pintype "input"))
    )
    (net (code "61") (name "RXgps") (class "Default")
      (node (ref "P1") (pin "2") (pinfunction "2_2") (pintype "unspecified"))
      (node (ref "U1") (pin "27") (pinfunction "IO16_27") (pintype "unspecified"))
    )
    (net (code "62") (name "TXgps") (class "Default")
      (node (ref "P1") (pin "3") (pinfunction "3_3") (pintype "unspecified"))
      (node (ref "U1") (pin "28") (pinfunction "IO17_28") (pintype "unspecified"))
    )
    (net (code "63") (name "VBUS") (class "Default")
      (node (ref "D1") (pin "2") (pinfunction "2_2") (pintype "unspecified"))
      (node (ref "D4") (pin "2") (pinfunction "2_2") (pintype "unspecified"))
      (node (ref "R9") (pin "1") (pinfunction "1_1") (pintype "input"))
      (node (ref "USB1") (pin "1") (pinfunction "VBUS_1") (pintype "bidirectional"))
    )
    (net (code "64") (name "Vin") (class "Default")
      (node (ref "C19") (pin "2") (pinfunction "2_2") (pintype "unspecified"))
      (node (ref "C20") (pin "1") (pinfunction "1_1") (pintype "unspecified"))
      (node (ref "U12") (pin "1") (pinfunction "1_1") (pintype "unspecified"))
      (node (ref "U9") (pin "1") (pinfunction "Vin_1") (pintype "unspecified"))
    )
    (net (code "65") (name "Vout") (class "Default")
      (node (ref "D5") (pin "1") (pinfunction "K_1") (pintype "unspecified"))
      (node (ref "U10") (pin "1") (pinfunction "1_1") (pintype "unspecified"))
      (node (ref "U9") (pin "2") (pinfunction "Output_2") (pintype "unspecified"))
    )
    (net (code "66") (name "unconnected-(U1-CMD-Pad19)") (class "Default")
      (node (ref "U1") (pin "19") (pinfunction "CMD_19") (pintype "unspecified"))
    )
    (net (code "67") (name "unconnected-(U2-CHR0-Pad15)") (class "Default")
      (node (ref "U2") (pin "15") (pinfunction "CHR0_15") (pintype "unspecified+no_connect"))
    )
    (net (code "68") (name "unconnected-(U2-CHR1-Pad14)") (class "Default")
      (node (ref "U2") (pin "14") (pinfunction "CHR1_14") (pintype "unspecified+no_connect"))
    )
    (net (code "69") (name "unconnected-(U2-CHREN-Pad13)") (class "Default")
      (node (ref "U2") (pin "13") (pinfunction "CHREN_13") (pintype "unspecified+no_connect"))
    )
    (net (code "70") (name "unconnected-(U2-EXP-Pad29)") (class "Default")
      (node (ref "U2") (pin "29") (pinfunction "EXP_29") (pintype "unspecified+no_connect"))
    )
    (net (code "71") (name "unconnected-(U2-GPIO.0{slash}TXT-Pad19)") (class "Default")
      (node (ref "U2") (pin "19") (pinfunction "GPIO.0/TXT_19") (pintype "unspecified+no_connect"))
    )
    (net (code "72") (name "unconnected-(U2-GPIO.1{slash}RXT-Pad18)") (class "Default")
      (node (ref "U2") (pin "18") (pinfunction "GPIO.1/RXT_18") (pintype "unspecified+no_connect"))
    )
    (net (code "73") (name "unconnected-(U2-GPIO.2{slash}RS485-Pad17)") (class "Default")
      (node (ref "U2") (pin "17") (pinfunction "GPIO.2/RS485_17") (pintype "unspecified+no_connect"))
    )
    (net (code "74") (name "unconnected-(U2-GPIO.3{slash}WAKEUP-Pad16)") (class "Default")
      (node (ref "U2") (pin "16") (pinfunction "GPIO.3/WAKEUP_16") (pintype "unspecified+no_connect"))
    )
    (net (code "75") (name "unconnected-(U2-GPIO.4-Pad22)") (class "Default")
      (node (ref "U2") (pin "22") (pinfunction "GPIO.4_22") (pintype "unspecified+no_connect"))
    )
    (net (code "76") (name "unconnected-(U2-GPIO.5-Pad21)") (class "Default")
      (node (ref "U2") (pin "21") (pinfunction "GPIO.5_21") (pintype "unspecified+no_connect"))
    )
    (net (code "77") (name "unconnected-(U2-GPIO.6-Pad20)") (class "Default")
      (node (ref "U2") (pin "20") (pinfunction "GPIO.6_20") (pintype "unspecified+no_connect"))
    )
    (net (code "78") (name "unconnected-(U2-NC-Pad10)") (class "Default")
      (node (ref "U2") (pin "10") (pinfunction "NC_10") (pintype "unspecified+no_connect"))
    )
    (net (code "79") (name "unconnected-(U2-SUSPEND-Pad12)") (class "Default")
      (node (ref "U2") (pin "12") (pinfunction "SUSPEND_12") (pintype "unspecified+no_connect"))
    )
    (net (code "80") (name "unconnected-(U3-VOUT-Pad2)") (class "Default")
      (node (ref "U3") (pin "2") (pinfunction "VOUT_2") (pintype "unspecified"))
    )
    (net (code "81") (name "unconnected-(U4-AUX_CL-Pad7)") (class "Default")
      (node (ref "U4") (pin "7") (pinfunction "AUX_CL_7") (pintype "unspecified"))
    )
    (net (code "82") (name "unconnected-(U4-AUX_DA-Pad6)") (class "Default")
      (node (ref "U4") (pin "6") (pinfunction "AUX_DA_6") (pintype "unspecified"))
    )
    (net (code "83") (name "unconnected-(U4-EP-Pad25)") (class "Default")
      (node (ref "U4") (pin "25") (pinfunction "EP_25") (pintype "unspecified"))
    )
    (net (code "84") (name "unconnected-(U4-NC-Pad2)") (class "Default")
      (node (ref "U4") (pin "2") (pinfunction "NC_2") (pintype "unspecified+no_connect"))
    )
    (net (code "85") (name "unconnected-(U4-NC-Pad3)") (class "Default")
      (node (ref "U4") (pin "3") (pinfunction "NC_3") (pintype "unspecified+no_connect"))
    )
    (net (code "86") (name "unconnected-(U4-NC-Pad4)") (class "Default")
      (node (ref "U4") (pin "4") (pinfunction "NC_4") (pintype "unspecified+no_connect"))
    )
    (net (code "87") (name "unconnected-(U4-NC-Pad5)") (class "Default")
      (node (ref "U4") (pin "5") (pinfunction "NC_5") (pintype "unspecified+no_connect"))
    )
    (net (code "88") (name "unconnected-(U4-NC-Pad14)") (class "Default")
      (node (ref "U4") (pin "14") (pinfunction "NC_14") (pintype "unspecified+no_connect"))
    )
    (net (code "89") (name "unconnected-(U4-NC-Pad15)") (class "Default")
      (node (ref "U4") (pin "15") (pinfunction "NC_15") (pintype "unspecified+no_connect"))
    )
    (net (code "90") (name "unconnected-(U4-NC-Pad16)") (class "Default")
      (node (ref "U4") (pin "16") (pinfunction "NC_16") (pintype "unspecified+no_connect"))
    )
    (net (code "91") (name "unconnected-(U4-NC-Pad17)") (class "Default")
      (node (ref "U4") (pin "17") (pinfunction "NC_17") (pintype "unspecified+no_connect"))
    )
    (net (code "92") (name "unconnected-(U4-RESV-Pad19)") (class "Default")
      (node (ref "U4") (pin "19") (pinfunction "RESV_19") (pintype "unspecified"))
    )
    (net (code "93") (name "unconnected-(U4-RESV-Pad21)") (class "Default")
      (node (ref "U4") (pin "21") (pinfunction "RESV_21") (pintype "unspecified"))
    )
    (net (code "94") (name "unconnected-(U4-RESV-Pad22)") (class "Default")
      (node (ref "U4") (pin "22") (pinfunction "RESV_22") (pintype "unspecified"))
    )
    (net (code "95") (name "unconnected-(U5-CSB-Pad1)") (class "Default")
      (node (ref "U5") (pin "1") (pinfunction "CSB_1") (pintype "unspecified+no_connect"))
    )
    (net (code "96") (name "unconnected-(U5-SDO-Pad4)") (class "Default")
      (node (ref "U5") (pin "4") (pinfunction "SDO_4") (pintype "unspecified+no_connect"))
    )
    (net (code "97") (name "unconnected-(U7-HOLD#(IO3)-Pad7)") (class "Default")
      (node (ref "U7") (pin "7") (pinfunction "HOLD#(IO3)_7") (pintype "unspecified+no_connect"))
    )
    (net (code "98") (name "unconnected-(U7-WP#(IO2)-Pad3)") (class "Default")
      (node (ref "U7") (pin "3") (pinfunction "WP#(IO2)_3") (pintype "unspecified+no_connect"))
    )
    (net (code "99") (name "unconnected-(U8-HOLD#(IO3)-Pad7)") (class "Default")
      (node (ref "U8") (pin "7") (pinfunction "HOLD#(IO3)_7") (pintype "unspecified+no_connect"))
    )
    (net (code "100") (name "unconnected-(U8-WP#(IO2)-Pad3)") (class "Default")
      (node (ref "U8") (pin "3") (pinfunction "WP#(IO2)_3") (pintype "unspecified+no_connect"))
    )
    (net (code "101") (name "unconnected-(U9-TAB-Pad6)") (class "Default")
      (node (ref "U9") (pin "6") (pinfunction "TAB_6") (pintype "unspecified"))
    )
    (net (code "102") (name "unconnected-(U11-VOUT-Pad2)") (class "Default")
      (node (ref "U11") (pin "2") (pinfunction "VOUT_2") (pintype "unspecified"))
    )
    (net (code "103") (name "unconnected-(USB1-ID-Pad4)") (class "Default")
      (node (ref "USB1") (pin "4") (pinfunction "ID_4") (pintype "bidirectional+no_connect"))
    )
    (net (code "104") (name "unconnected-(USB1-Pad6)") (class "Default")
      (node (ref "USB1") (pin "6") (pintype "unspecified+no_connect"))
    )
  )
)
